# TpIntegradorSch.net
KiCad netlist of a schematic drawn in Altium Designer
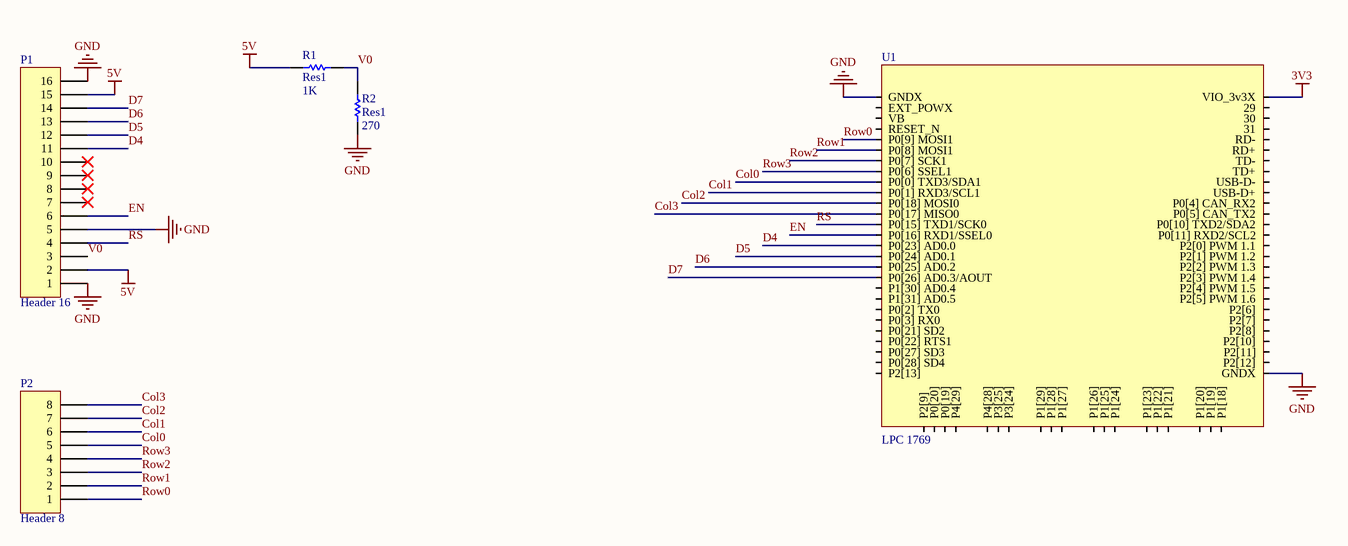
[diagram p0: TpIntegradorSch.SchDoc]

(export (version "E")
  (design (tool "Eeschema 10.0.6"))
  (components
    (comp (ref "P1")
      (value "Header 16")
      (footprint "HDR1X16")
      (description "Header, 16-Pin")
      (fields (field (name "PUBLISHER") "Altium Limited"))
      (libsource (lib "Miscellaneous Connectors") (part "Header 16"))
    )
    (comp (ref "P2")
      (value "Header 8")
      (footprint "HDR1X8")
      (description "Header, 8-Pin")
      (fields (field (name "PUBLISHER") "Altium Limited"))
      (libsource (lib "Miscellaneous Connectors") (part "Header 8"))
    )
    (comp (ref "R1")
      (value "Res1")
      (footprint "AXIAL-0.3")
      (description "Resistor")
      (fields (field (name "ALTIUM_VALUE") "1K") (field (name "PUBLISHER") "Altium Limited"))
      (libsource (lib "Miscellaneous Devices") (part "Res1"))
    )
    (comp (ref "R2")
      (value "Res1")
      (footprint "AXIAL-0.3")
      (description "Resistor")
      (fields (field (name "ALTIUM_VALUE") "270") (field (name "PUBLISHER") "Altium Limited"))
      (libsource (lib "Miscellaneous Devices") (part "Res1"))
    )
    (comp (ref "U1")
      (value "LPC 1769")
      (footprint "LPC 1769")
      (libsource (lib "LPC1769Library") (part "LPC 1769"))
    )
  )
  (nets
    (net (code "1") (name "/Col0") (class "Default")
      (node (ref "P2") (pin "5") (pinfunction "5_5") (pintype "passive"))
      (node (ref "U1") (pin "9") (pinfunction "P0[0]_TXD3/SDA1_9") (pintype "passive"))
    )
    (net (code "2") (name "/Col1") (class "Default")
      (node (ref "P2") (pin "6") (pinfunction "6_6") (pintype "passive"))
      (node (ref "U1") (pin "10") (pinfunction "P0[1]_RXD3/SCL1_10") (pintype "passive"))
    )
    (net (code "3") (name "/Col2") (class "Default")
      (node (ref "P2") (pin "7") (pinfunction "7_7") (pintype "passive"))
      (node (ref "U1") (pin "11") (pinfunction "P0[18]_MOSI0_11") (pintype "passive"))
    )
    (net (code "4") (name "/Col3") (class "Default")
      (node (ref "P2") (pin "8") (pinfunction "8_8") (pintype "passive"))
      (node (ref "U1") (pin "12") (pinfunction "P0[17]_MISO0_12") (pintype "passive"))
    )
    (net (code "5") (name "/D4") (class "Default")
      (node (ref "P1") (pin "11") (pinfunction "11_11") (pintype "passive"))
      (node (ref "U1") (pin "15") (pinfunction "P0[23]_AD0.0_15") (pintype "passive"))
    )
    (net (code "6") (name "/D5") (class "Default")
      (node (ref "P1") (pin "12") (pinfunction "12_12") (pintype "passive"))
      (node (ref "U1") (pin "16") (pinfunction "P0[24]_AD0.1_16") (pintype "passive"))
    )
    (net (code "7") (name "/D6") (class "Default")
      (node (ref "P1") (pin "13") (pinfunction "13_13") (pintype "passive"))
      (node (ref "U1") (pin "17") (pinfunction "P0[25]_AD0.2_17") (pintype "passive"))
    )
    (net (code "8") (name "/D7") (class "Default")
      (node (ref "P1") (pin "14") (pinfunction "14_14") (pintype "passive"))
      (node (ref "U1") (pin "18") (pinfunction "P0[26]_AD0.3/AOUT_18") (pintype "passive"))
    )
    (net (code "9") (name "/EN") (class "Default")
      (node (ref "P1") (pin "6") (pinfunction "6_6") (pintype "passive"))
      (node (ref "U1") (pin "14") (pinfunction "P0[16]_RXD1/SSEL0_14") (pintype "passive"))
    )
    (net (code "10") (name "/RS") (class "Default")
      (node (ref "P1") (pin "4") (pinfunction "4_4") (pintype "passive"))
      (node (ref "U1") (pin "13") (pinfunction "P0[15]_TXD1/SCK0_13") (pintype "passive"))
    )
    (net (code "11") (name "/Row0") (class "Default")
      (node (ref "P2") (pin "1") (pinfunction "1_1") (pintype "passive"))
      (node (ref "U1") (pin "5") (pinfunction "P0[9]_MOSI1_5") (pintype "passive"))
    )
    (net (code "12") (name "/Row1") (class "Default")
      (node (ref "P2") (pin "2") (pinfunction "2_2") (pintype "passive"))
      (node (ref "U1") (pin "6") (pinfunction "P0[8]_MOSI1_6") (pintype "passive"))
    )
    (net (code "13") (name "/Row2") (class "Default")
      (node (ref "P2") (pin "3") (pinfunction "3_3") (pintype "passive"))
      (node (ref "U1") (pin "7") (pinfunction "P0[7]_SCK1_7") (pintype "passive"))
    )
    (net (code "14") (name "/Row3") (class "Default")
      (node (ref "P2") (pin "4") (pinfunction "4_4") (pintype "passive"))
      (node (ref "U1") (pin "8") (pinfunction "P0[6]_SSEL1_8") (pintype "passive"))
    )
    (net (code "15") (name "/V0") (class "Default")
      (node (ref "P1") (pin "3") (pinfunction "3_3") (pintype "passive"))
      (node (ref "R1") (pin "2") (pinfunction "2_2") (pintype "passive"))
      (node (ref "R2") (pin "2") (pinfunction "2_2") (pintype "passive"))
    )
    (net (code "16") (name "3V3") (class "Default")
      (node (ref "U1") (pin "28") (pinfunction "VIO_3v3X_28") (pintype "passive"))
    )
    (net (code "17") (name "5V") (class "Default")
      (node (ref "P1") (pin "15") (pinfunction "15_15") (pintype "passive"))
      (node (ref "P1") (pin "2") (pinfunction "2_2") (pintype "passive"))
      (node (ref "R1") (pin "1") (pinfunction "1_1") (pintype "passive"))
    )
    (net (code "18") (name "GND") (class "Default")
      (node (ref "P1") (pin "1") (pinfunction "1_1") (pintype "passive"))
      (node (ref "P1") (pin "16") (pinfunction "16_16") (pintype "passive"))
      (node (ref "P1") (pin "5") (pinfunction "5_5") (pintype "passive"))
      (node (ref "R2") (pin "1") (pinfunction "1_1") (pintype "passive"))
      (node (ref "U1") (pin "1") (pinfunction "GNDX_1") (pintype "passive"))
      (node (ref "U1") (pin "54") (pinfunction "GNDX_54") (pintype "passive"))
    )
    (net (code "19") (name "unconnected-(P1-Pad7)") (class "Default")
      (node (ref "P1") (pin "7") (pinfunction "7_7") (pintype "passive+no_connect"))
    )
    (net (code "20") (name "unconnected-(P1-Pad8)") (class "Default")
      (node (ref "P1") (pin "8") (pinfunction "8_8") (pintype "passive+no_connect"))
    )
    (net (code "21") (name "unconnected-(P1-Pad9)") (class "Default")
      (node (ref "P1") (pin "9") (pinfunction "9_9") (pintype "passive+no_connect"))
    )
    (net (code "22") (name "unconnected-(P1-Pad10)") (class "Default")
      (node (ref "P1") (pin "10") (pinfunction "10_10") (pintype "passive+no_connect"))
    )
    (net (code "23") (name "unconnected-(U1-EXT_POWX-Pad2)") (class "Default")
      (node (ref "U1") (pin "2") (pinfunction "EXT_POWX_2") (pintype "passive"))
    )
    (net (code "24") (name "unconnected-(U1-P0[2]_TX0-Pad21)") (class "Default")
      (node (ref "U1") (pin "21") (pinfunction "P0[2]_TX0_21") (pintype "passive"))
    )
    (net (code "25") (name "unconnected-(U1-P0[3]_RX0-Pad22)") (class "Default")
      (node (ref "U1") (pin "22") (pinfunction "P0[3]_RX0_22") (pintype "passive"))
    )
    (net (code "26") (name "unconnected-(U1-P0[4]_CAN_RX2-Pad38)") (class "Default")
      (node (ref "U1") (pin "38") (pinfunction "P0[4]_CAN_RX2_38") (pintype "passive"))
    )
    (net (code "27") (name "unconnected-(U1-P0[5]_CAN_TX2-Pad39)") (class "Default")
      (node (ref "U1") (pin "39") (pinfunction "P0[5]_CAN_TX2_39") (pintype "passive"))
    )
    (net (code "28") (name "unconnected-(U1-P0[10]_TXD2{slash}SDA2-Pad40)") (class "Default")
      (node (ref "U1") (pin "40") (pinfunction "P0[10]_TXD2/SDA2_40") (pintype "passive"))
    )
    (net (code "29") (name "unconnected-(U1-P0[11]_RXD2{slash}SCL2-Pad41)") (class "Default")
      (node (ref "U1") (pin "41") (pinfunction "P0[11]_RXD2/SCL2_41") (pintype "passive"))
    )
    (net (code "30") (name "unconnected-(U1-P0[19]-Pad62)") (class "Default")
      (node (ref "U1") (pin "62") (pinfunction "P0[19]_62") (pintype "passive"))
    )
    (net (code "31") (name "unconnected-(U1-P0[20]-Pad56)") (class "Default")
      (node (ref "U1") (pin "56") (pinfunction "P0[20]_56") (pintype "passive"))
    )
    (net (code "32") (name "unconnected-(U1-P0[21]_SD2-Pad23)") (class "Default")
      (node (ref "U1") (pin "23") (pinfunction "P0[21]_SD2_23") (pintype "passive"))
    )
    (net (code "33") (name "unconnected-(U1-P0[22]_RTS1-Pad24)") (class "Default")
      (node (ref "U1") (pin "24") (pinfunction "P0[22]_RTS1_24") (pintype "passive"))
    )
    (net (code "34") (name "unconnected-(U1-P0[27]_SD3-Pad25)") (class "Default")
      (node (ref "U1") (pin "25") (pinfunction "P0[27]_SD3_25") (pintype "passive"))
    )
    (net (code "35") (name "unconnected-(U1-P0[28]_SD4-Pad26)") (class "Default")
      (node (ref "U1") (pin "26") (pinfunction "P0[28]_SD4_26") (pintype "passive"))
    )
    (net (code "36") (name "unconnected-(U1-P1[18]-Pad73)") (class "Default")
      (node (ref "U1") (pin "73") (pinfunction "P1[18]_73") (pintype "passive"))
    )
    (net (code "37") (name "unconnected-(U1-P1[19]-Pad67)") (class "Default")
      (node (ref "U1") (pin "67") (pinfunction "P1[19]_67") (pintype "passive"))
    )
    (net (code "38") (name "unconnected-(U1-P1[20]-Pad61)") (class "Default")
      (node (ref "U1") (pin "61") (pinfunction "P1[20]_61") (pintype "passive"))
    )
    (net (code "39") (name "unconnected-(U1-P1[21]-Pad72)") (class "Default")
      (node (ref "U1") (pin "72") (pinfunction "P1[21]_72") (pintype "passive"))
    )
    (net (code "40") (name "unconnected-(U1-P1[22]-Pad66)") (class "Default")
      (node (ref "U1") (pin "66") (pinfunction "P1[22]_66") (pintype "passive"))
    )
    (net (code "41") (name "unconnected-(U1-P1[23]-Pad60)") (class "Default")
      (node (ref "U1") (pin "60") (pinfunction "P1[23]_60") (pintype "passive"))
    )
    (net (code "42") (name "unconnected-(U1-P1[24]-Pad71)") (class "Default")
      (node (ref "U1") (pin "71") (pinfunction "P1[24]_71") (pintype "passive"))
    )
    (net (code "43") (name "unconnected-(U1-P1[25]-Pad65)") (class "Default")
      (node (ref "U1") (pin "65") (pinfunction "P1[25]_65") (pintype "passive"))
    )
    (net (code "44") (name "unconnected-(U1-P1[26]-Pad59)") (class "Default")
      (node (ref "U1") (pin "59") (pinfunction "P1[26]_59") (pintype "passive"))
    )
    (net (code "45") (name "unconnected-(U1-P1[27]-Pad70)") (class "Default")
      (node (ref "U1") (pin "70") (pinfunction "P1[27]_70") (pintype "passive"))
    )
    (net (code "46") (name "unconnected-(U1-P1[28]-Pad64)") (class "Default")
      (node (ref "U1") (pin "64") (pinfunction "P1[28]_64") (pintype "passive"))
    )
    (net (code "47") (name "unconnected-(U1-P1[29]-Pad58)") (class "Default")
      (node (ref "U1") (pin "58") (pinfunction "P1[29]_58") (pintype "passive"))
    )
    (net (code "48") (name "unconnected-(U1-P1[30]_AD0.4-Pad19)") (class "Default")
      (node (ref "U1") (pin "19") (pinfunction "P1[30]_AD0.4_19") (pintype "passive"))
    )
    (net (code "49") (name "unconnected-(U1-P1[31]_AD0.5-Pad20)") (class "Default")
      (node (ref "U1") (pin "20") (pinfunction "P1[31]_AD0.5_20") (pintype "passive"))
    )
    (net (code "50") (name "unconnected-(U1-P2[0]_PWM_1.1-Pad42)") (class "Default")
      (node (ref "U1") (pin "42") (pinfunction "P2[0]_PWM_1.1_42") (pintype "passive"))
    )
    (net (code "51") (name "unconnected-(U1-P2[1]_PWM_1.2-Pad43)") (class "Default")
      (node (ref "U1") (pin "43") (pinfunction "P2[1]_PWM_1.2_43") (pintype "passive"))
    )
    (net (code "52") (name "unconnected-(U1-P2[2]_PWM_1.3-Pad44)") (class "Default")
      (node (ref "U1") (pin "44") (pinfunction "P2[2]_PWM_1.3_44") (pintype "passive"))
    )
    (net (code "53") (name "unconnected-(U1-P2[3]_PWM_1.4-Pad45)") (class "Default")
      (node (ref "U1") (pin "45") (pinfunction "P2[3]_PWM_1.4_45") (pintype "passive"))
    )
    (net (code "54") (name "unconnected-(U1-P2[4]_PWM_1.5-Pad46)") (class "Default")
      (node (ref "U1") (pin "46") (pinfunction "P2[4]_PWM_1.5_46") (pintype "passive"))
    )
    (net (code "55") (name "unconnected-(U1-P2[5]_PWM_1.6-Pad47)") (class "Default")
      (node (ref "U1") (pin "47") (pinfunction "P2[5]_PWM_1.6_47") (pintype "passive"))
    )
    (net (code "56") (name "unconnected-(U1-P2[6]-Pad48)") (class "Default")
      (node (ref "U1") (pin "48") (pinfunction "P2[6]_48") (pintype "passive"))
    )
    (net (code "57") (name "unconnected-(U1-P2[7]-Pad49)") (class "Default")
      (node (ref "U1") (pin "49") (pinfunction "P2[7]_49") (pintype "passive"))
    )
    (net (code "58") (name "unconnected-(U1-P2[8]-Pad50)") (class "Default")
      (node (ref "U1") (pin "50") (pinfunction "P2[8]_50") (pintype "passive"))
    )
    (net (code "59") (name "unconnected-(U1-P2[9]-Pad55)") (class "Default")
      (node (ref "U1") (pin "55") (pinfunction "P2[9]_55") (pintype "passive"))
    )
    (net (code "60") (name "unconnected-(U1-P2[10]-Pad51)") (class "Default")
      (node (ref "U1") (pin "51") (pinfunction "P2[10]_51") (pintype "passive"))
    )
    (net (code "61") (name "unconnected-(U1-P2[11]-Pad52)") (class "Default")
      (node (ref "U1") (pin "52") (pinfunction "P2[11]_52") (pintype "passive"))
    )
    (net (code "62") (name "unconnected-(U1-P2[12]-Pad53)") (class "Default")
      (node (ref "U1") (pin "53") (pinfunction "P2[12]_53") (pintype "passive"))
    )
    (net (code "63") (name "unconnected-(U1-P2[13]-Pad27)") (class "Default")
      (node (ref "U1") (pin "27") (pinfunction "P2[13]_27") (pintype "passive"))
    )
    (net (code "64") (name "unconnected-(U1-P3[24]-Pad69)") (class "Default")
      (node (ref "U1") (pin "69") (pinfunction "P3[24]_69") (pintype "passive"))
    )
    (net (code "65") (name "unconnected-(U1-P3[25]-Pad63)") (class "Default")
      (node (ref "U1") (pin "63") (pinfunction "P3[25]_63") (pintype "passive"))
    )
    (net (code "66") (name "unconnected-(U1-P4[28]-Pad57)") (class "Default")
      (node (ref "U1") (pin "57") (pinfunction "P4[28]_57") (pintype "passive"))
    )
    (net (code "67") (name "unconnected-(U1-P4[29]-Pad68)") (class "Default")
      (node (ref "U1") (pin "68") (pinfunction "P4[29]_68") (pintype "passive"))
    )
    (net (code "68") (name "unconnected-(U1-Pad29)") (class "Default")
      (node (ref "U1") (pin "29") (pinfunction "29_29") (pintype "passive"))
    )
    (net (code "69") (name "unconnected-(U1-Pad30)") (class "Default")
      (node (ref "U1") (pin "30") (pinfunction "30_30") (pintype "passive"))
    )
    (net (code "70") (name "unconnected-(U1-Pad31)") (class "Default")
      (node (ref "U1") (pin "31") (pinfunction "31_31") (pintype "passive"))
    )
    (net (code "71") (name "unconnected-(U1-RD+-Pad33)") (class "Default")
      (node (ref "U1") (pin "33") (pinfunction "RD+_33") (pintype "passive"))
    )
    (net (code "72") (name "unconnected-(U1-RD--Pad32)") (class "Default")
      (node (ref "U1") (pin "32") (pinfunction "RD-_32") (pintype "passive"))
    )
    (net (code "73") (name "unconnected-(U1-RESET_N-Pad4)") (class "Default")
      (node (ref "U1") (pin "4") (pinfunction "RESET_N_4") (pintype "passive"))
    )
    (net (code "74") (name "unconnected-(U1-TD+-Pad35)") (class "Default")
      (node (ref "U1") (pin "35") (pinfunction "TD+_35") (pintype "passive"))
    )
    (net (code "75") (name "unconnected-(U1-TD--Pad34)") (class "Default")
      (node (ref "U1") (pin "34") (pinfunction "TD-_34") (pintype "passive"))
    )
    (net (code "76") (name "unconnected-(U1-USB-D+-Pad37)") (class "Default")
      (node (ref "U1") (pin "37") (pinfunction "USB-D+_37") (pintype "passive"))
    )
    (net (code "77") (name "unconnected-(U1-USB-D--Pad36)") (class "Default")
      (node (ref "U1") (pin "36") (pinfunction "USB-D-_36") (pintype "passive"))
    )
    (net (code "78") (name "unconnected-(U1-VB-Pad3)") (class "Default")
      (node (ref "U1") (pin "3") (pinfunction "VB_3") (pintype "passive"))
    )
  )
)
